# Audio.net
KiCad netlist of a schematic drawn in Altium Designer
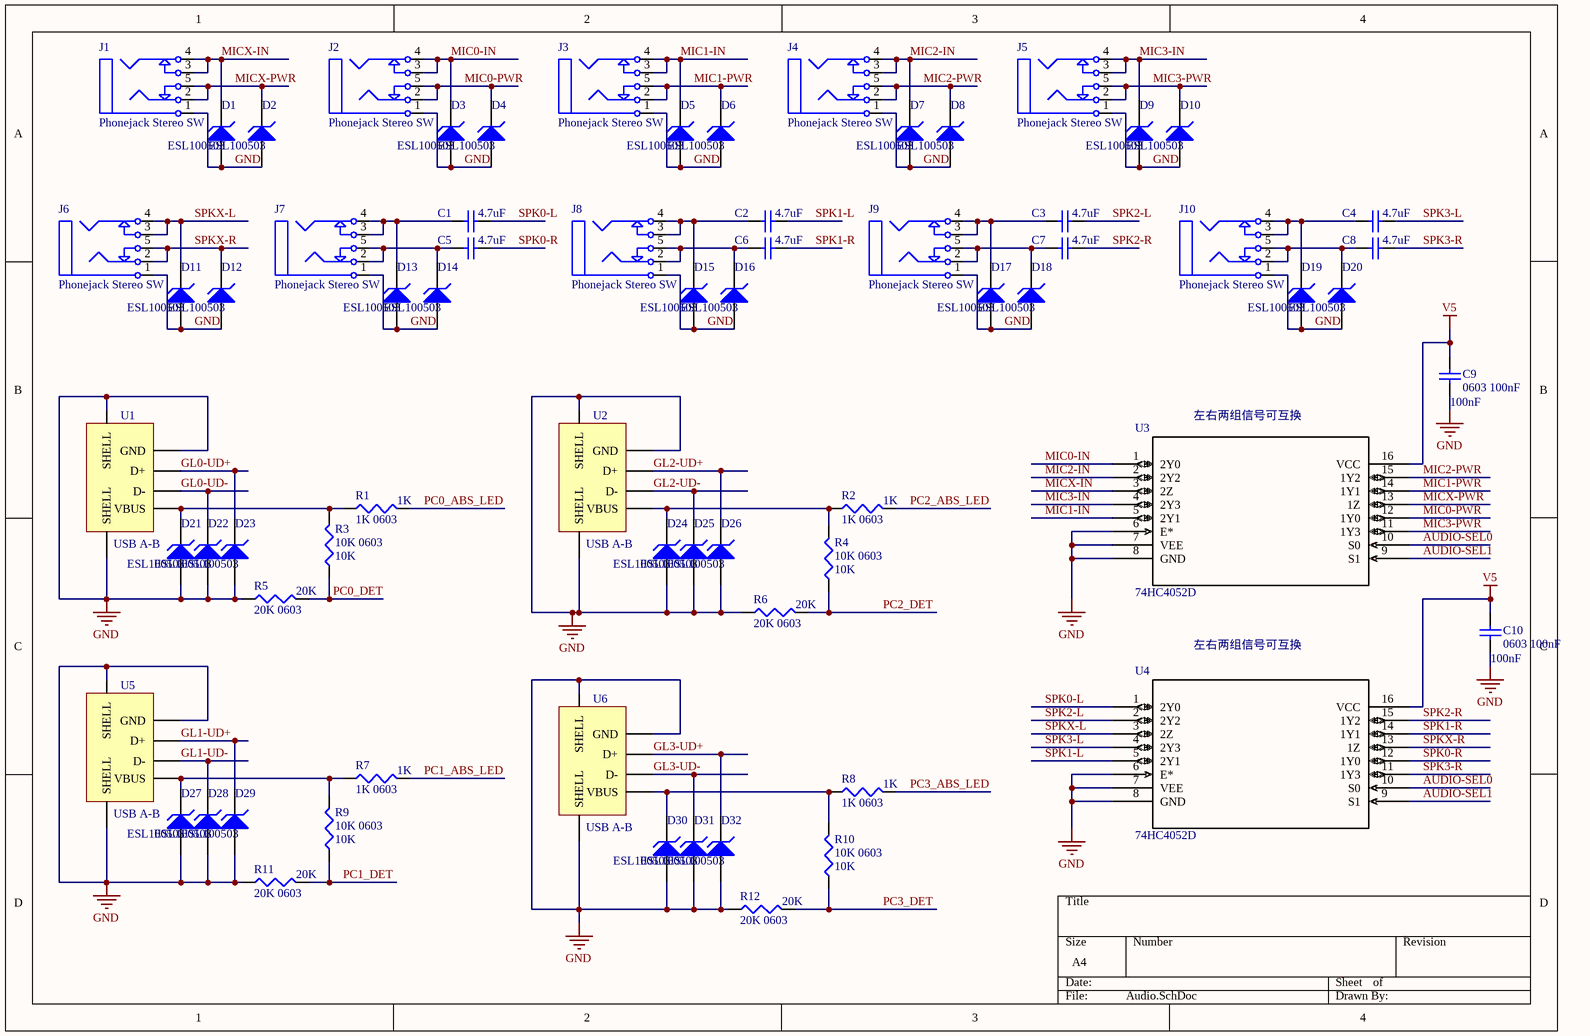
[diagram p0: Audio.SchDoc]

(export (version "E")
  (design (tool "Eeschema 10.0.6"))
  (components
    (comp (ref "C1")
      (value "4.7uF")
      (footprint "C0603")
      (description "Capacitor (Semiconductor SIM Model)")
      (fields (field (name "Comment") "0603 4.7uF") (field (name "PUBLISHER") "Altium Limited"))
      (libsource (lib "Miscellaneous Devices") (part "Cap Semi"))
    )
    (comp (ref "C2")
      (value "4.7uF")
      (footprint "C0603")
      (description "Capacitor (Semiconductor SIM Model)")
      (fields (field (name "Comment") "0603 4.7uF") (field (name "PUBLISHER") "Altium Limited"))
      (libsource (lib "Miscellaneous Devices") (part "Cap Semi"))
    )
    (comp (ref "C3")
      (value "4.7uF")
      (footprint "C0603")
      (description "Capacitor (Semiconductor SIM Model)")
      (fields (field (name "Comment") "0603 4.7uF") (field (name "PUBLISHER") "Altium Limited"))
      (libsource (lib "Miscellaneous Devices") (part "Cap Semi"))
    )
    (comp (ref "C4")
      (value "4.7uF")
      (footprint "C0603")
      (description "Capacitor (Semiconductor SIM Model)")
      (fields (field (name "Comment") "0603 4.7uF") (field (name "PUBLISHER") "Altium Limited"))
      (libsource (lib "Miscellaneous Devices") (part "Cap Semi"))
    )
    (comp (ref "C5")
      (value "4.7uF")
      (footprint "C0603")
      (description "Capacitor (Semiconductor SIM Model)")
      (fields (field (name "Comment") "0603 4.7uF") (field (name "PUBLISHER") "Altium Limited"))
      (libsource (lib "Miscellaneous Devices") (part "Cap Semi"))
    )
    (comp (ref "C6")
      (value "4.7uF")
      (footprint "C0603")
      (description "Capacitor (Semiconductor SIM Model)")
      (fields (field (name "Comment") "0603 4.7uF") (field (name "PUBLISHER") "Altium Limited"))
      (libsource (lib "Miscellaneous Devices") (part "Cap Semi"))
    )
    (comp (ref "C7")
      (value "4.7uF")
      (footprint "C0603")
      (description "Capacitor (Semiconductor SIM Model)")
      (fields (field (name "Comment") "0603 4.7uF") (field (name "PUBLISHER") "Altium Limited"))
      (libsource (lib "Miscellaneous Devices") (part "Cap Semi"))
    )
    (comp (ref "C8")
      (value "4.7uF")
      (footprint "C0603")
      (description "Capacitor (Semiconductor SIM Model)")
      (fields (field (name "Comment") "0603 4.7uF") (field (name "PUBLISHER") "Altium Limited"))
      (libsource (lib "Miscellaneous Devices") (part "Cap Semi"))
    )
    (comp (ref "C9")
      (value "0603 100nF")
      (footprint "C0603")
      (description "Capacitor (Semiconductor SIM Model)")
      (fields (field (name "ALTIUM_VALUE") "100nF") (field (name "PUBLISHER") "Altium Limited"))
      (libsource (lib "Miscellaneous Devices") (part "Cap Semi"))
    )
    (comp (ref "C10")
      (value "0603 100nF")
      (footprint "C0603")
      (description "Capacitor (Semiconductor SIM Model)")
      (fields (field (name "ALTIUM_VALUE") "100nF") (field (name "PUBLISHER") "Altium Limited"))
      (libsource (lib "Miscellaneous Devices") (part "Cap Semi"))
    )
    (comp (ref "D1")
      (value "ESL100503")
      (footprint "C0402")
      (fields (field (name "PUBLISHER") "Altium Limited"))
      (libsource (lib "Miscellaneous Devices") (part "D Zener"))
    )
    (comp (ref "D2")
      (value "ESL100503")
      (footprint "C0402")
      (fields (field (name "PUBLISHER") "Altium Limited"))
      (libsource (lib "Miscellaneous Devices") (part "D Zener"))
    )
    (comp (ref "D3")
      (value "ESL100503")
      (footprint "C0402")
      (fields (field (name "PUBLISHER") "Altium Limited"))
      (libsource (lib "Miscellaneous Devices") (part "D Zener"))
    )
    (comp (ref "D4")
      (value "ESL100503")
      (footprint "C0402")
      (fields (field (name "PUBLISHER") "Altium Limited"))
      (libsource (lib "Miscellaneous Devices") (part "D Zener"))
    )
    (comp (ref "D5")
      (value "ESL100503")
      (footprint "C0402")
      (fields (field (name "PUBLISHER") "Altium Limited"))
      (libsource (lib "Miscellaneous Devices") (part "D Zener"))
    )
    (comp (ref "D6")
      (value "ESL100503")
      (footprint "C0402")
      (fields (field (name "PUBLISHER") "Altium Limited"))
      (libsource (lib "Miscellaneous Devices") (part "D Zener"))
    )
    (comp (ref "D7")
      (value "ESL100503")
      (footprint "C0402")
      (fields (field (name "PUBLISHER") "Altium Limited"))
      (libsource (lib "Miscellaneous Devices") (part "D Zener"))
    )
    (comp (ref "D8")
      (value "ESL100503")
      (footprint "C0402")
      (fields (field (name "PUBLISHER") "Altium Limited"))
      (libsource (lib "Miscellaneous Devices") (part "D Zener"))
    )
    (comp (ref "D9")
      (value "ESL100503")
      (footprint "C0402")
      (fields (field (name "PUBLISHER") "Altium Limited"))
      (libsource (lib "Miscellaneous Devices") (part "D Zener"))
    )
    (comp (ref "D10")
      (value "ESL100503")
      (footprint "C0402")
      (fields (field (name "PUBLISHER") "Altium Limited"))
      (libsource (lib "Miscellaneous Devices") (part "D Zener"))
    )
    (comp (ref "D11")
      (value "ESL100503")
      (footprint "C0402")
      (fields (field (name "PUBLISHER") "Altium Limited"))
      (libsource (lib "Miscellaneous Devices") (part "D Zener"))
    )
    (comp (ref "D12")
      (value "ESL100503")
      (footprint "C0402")
      (fields (field (name "PUBLISHER") "Altium Limited"))
      (libsource (lib "Miscellaneous Devices") (part "D Zener"))
    )
    (comp (ref "D13")
      (value "ESL100503")
      (footprint "C0402")
      (fields (field (name "PUBLISHER") "Altium Limited"))
      (libsource (lib "Miscellaneous Devices") (part "D Zener"))
    )
    (comp (ref "D14")
      (value "ESL100503")
      (footprint "C0402")
      (fields (field (name "PUBLISHER") "Altium Limited"))
      (libsource (lib "Miscellaneous Devices") (part "D Zener"))
    )
    (comp (ref "D15")
      (value "ESL100503")
      (footprint "C0402")
      (fields (field (name "PUBLISHER") "Altium Limited"))
      (libsource (lib "Miscellaneous Devices") (part "D Zener"))
    )
    (comp (ref "D16")
      (value "ESL100503")
      (footprint "C0402")
      (fields (field (name "PUBLISHER") "Altium Limited"))
      (libsource (lib "Miscellaneous Devices") (part "D Zener"))
    )
    (comp (ref "D17")
      (value "ESL100503")
      (footprint "C0402")
      (fields (field (name "PUBLISHER") "Altium Limited"))
      (libsource (lib "Miscellaneous Devices") (part "D Zener"))
    )
    (comp (ref "D18")
      (value "ESL100503")
      (footprint "C0402")
      (fields (field (name "PUBLISHER") "Altium Limited"))
      (libsource (lib "Miscellaneous Devices") (part "D Zener"))
    )
    (comp (ref "D19")
      (value "ESL100503")
      (footprint "C0402")
      (fields (field (name "PUBLISHER") "Altium Limited"))
      (libsource (lib "Miscellaneous Devices") (part "D Zener"))
    )
    (comp (ref "D20")
      (value "ESL100503")
      (footprint "C0402")
      (fields (field (name "PUBLISHER") "Altium Limited"))
      (libsource (lib "Miscellaneous Devices") (part "D Zener"))
    )
    (comp (ref "D21")
      (value "ESL100503")
      (footprint "C0402")
      (fields (field (name "PUBLISHER") "Altium Limited"))
      (libsource (lib "Miscellaneous Devices") (part "D Zener"))
    )
    (comp (ref "D22")
      (value "ESL100503")
      (footprint "C0402")
      (fields (field (name "PUBLISHER") "Altium Limited"))
      (libsource (lib "Miscellaneous Devices") (part "D Zener"))
    )
    (comp (ref "D23")
      (value "ESL100503")
      (footprint "C0402")
      (fields (field (name "PUBLISHER") "Altium Limited"))
      (libsource (lib "Miscellaneous Devices") (part "D Zener"))
    )
    (comp (ref "D24")
      (value "ESL100503")
      (footprint "C0402")
      (fields (field (name "PUBLISHER") "Altium Limited"))
      (libsource (lib "Miscellaneous Devices") (part "D Zener"))
    )
    (comp (ref "D25")
      (value "ESL100503")
      (footprint "C0402")
      (fields (field (name "PUBLISHER") "Altium Limited"))
      (libsource (lib "Miscellaneous Devices") (part "D Zener"))
    )
    (comp (ref "D26")
      (value "ESL100503")
      (footprint "C0402")
      (fields (field (name "PUBLISHER") "Altium Limited"))
      (libsource (lib "Miscellaneous Devices") (part "D Zener"))
    )
    (comp (ref "D27")
      (value "ESL100503")
      (footprint "C0402")
      (fields (field (name "PUBLISHER") "Altium Limited"))
      (libsource (lib "Miscellaneous Devices") (part "D Zener"))
    )
    (comp (ref "D28")
      (value "ESL100503")
      (footprint "C0402")
      (fields (field (name "PUBLISHER") "Altium Limited"))
      (libsource (lib "Miscellaneous Devices") (part "D Zener"))
    )
    (comp (ref "D29")
      (value "ESL100503")
      (footprint "C0402")
      (fields (field (name "PUBLISHER") "Altium Limited"))
      (libsource (lib "Miscellaneous Devices") (part "D Zener"))
    )
    (comp (ref "D30")
      (value "ESL100503")
      (footprint "C0402")
      (fields (field (name "PUBLISHER") "Altium Limited"))
      (libsource (lib "Miscellaneous Devices") (part "D Zener"))
    )
    (comp (ref "D31")
      (value "ESL100503")
      (footprint "C0402")
      (fields (field (name "PUBLISHER") "Altium Limited"))
      (libsource (lib "Miscellaneous Devices") (part "D Zener"))
    )
    (comp (ref "D32")
      (value "ESL100503")
      (footprint "C0402")
      (fields (field (name "PUBLISHER") "Altium Limited"))
      (libsource (lib "Miscellaneous Devices") (part "D Zener"))
    )
    (comp (ref "J1")
      (value "Phonejack Stereo SW")
      (footprint "ST-3150-5N")
      (description "3-Conductor Jack with 2 break contacts (normals) and 2 auxiliary make contacts")
      (fields (field (name "PUBLISHER") "Altium Limited"))
      (libsource (lib "Miscellaneous Connectors") (part "Phonejack Stereo SW"))
    )
    (comp (ref "J2")
      (value "Phonejack Stereo SW")
      (footprint "ST-3150-5N")
      (description "3-Conductor Jack with 2 break contacts (normals) and 2 auxiliary make contacts")
      (fields (field (name "PUBLISHER") "Altium Limited"))
      (libsource (lib "Miscellaneous Connectors") (part "Phonejack Stereo SW"))
    )
    (comp (ref "J3")
      (value "Phonejack Stereo SW")
      (footprint "ST-3150-5N")
      (description "3-Conductor Jack with 2 break contacts (normals) and 2 auxiliary make contacts")
      (fields (field (name "PUBLISHER") "Altium Limited"))
      (libsource (lib "Miscellaneous Connectors") (part "Phonejack Stereo SW"))
    )
    (comp (ref "J4")
      (value "Phonejack Stereo SW")
      (footprint "ST-3150-5N")
      (description "3-Conductor Jack with 2 break contacts (normals) and 2 auxiliary make contacts")
      (fields (field (name "PUBLISHER") "Altium Limited"))
      (libsource (lib "Miscellaneous Connectors") (part "Phonejack Stereo SW"))
    )
    (comp (ref "J5")
      (value "Phonejack Stereo SW")
      (footprint "ST-3150-5N")
      (description "3-Conductor Jack with 2 break contacts (normals) and 2 auxiliary make contacts")
      (fields (field (name "PUBLISHER") "Altium Limited"))
      (libsource (lib "Miscellaneous Connectors") (part "Phonejack Stereo SW"))
    )
    (comp (ref "J6")
      (value "Phonejack Stereo SW")
      (footprint "ST-3150-5N")
      (description "3-Conductor Jack with 2 break contacts (normals) and 2 auxiliary make contacts")
      (fields (field (name "PUBLISHER") "Altium Limited"))
      (libsource (lib "Miscellaneous Connectors") (part "Phonejack Stereo SW"))
    )
    (comp (ref "J7")
      (value "Phonejack Stereo SW")
      (footprint "ST-3150-5N")
      (description "3-Conductor Jack with 2 break contacts (normals) and 2 auxiliary make contacts")
      (fields (field (name "PUBLISHER") "Altium Limited"))
      (libsource (lib "Miscellaneous Connectors") (part "Phonejack Stereo SW"))
    )
    (comp (ref "J8")
      (value "Phonejack Stereo SW")
      (footprint "ST-3150-5N")
      (description "3-Conductor Jack with 2 break contacts (normals) and 2 auxiliary make contacts")
      (fields (field (name "PUBLISHER") "Altium Limited"))
      (libsource (lib "Miscellaneous Connectors") (part "Phonejack Stereo SW"))
    )
    (comp (ref "J9")
      (value "Phonejack Stereo SW")
      (footprint "ST-3150-5N")
      (description "3-Conductor Jack with 2 break contacts (normals) and 2 auxiliary make contacts")
      (fields (field (name "PUBLISHER") "Altium Limited"))
      (libsource (lib "Miscellaneous Connectors") (part "Phonejack Stereo SW"))
    )
    (comp (ref "J10")
      (value "Phonejack Stereo SW")
      (footprint "ST-3150-5N")
      (description "3-Conductor Jack with 2 break contacts (normals) and 2 auxiliary make contacts")
      (fields (field (name "PUBLISHER") "Altium Limited"))
      (libsource (lib "Miscellaneous Connectors") (part "Phonejack Stereo SW"))
    )
    (comp (ref "R1")
      (value "1K 0603")
      (footprint "R0603")
      (description "Resistor")
      (fields (field (name "ALTIUM_VALUE") "1K") (field (name "PUBLISHER") "Altium Limited"))
      (libsource (lib "Miscellaneous Devices") (part "Res3"))
    )
    (comp (ref "R2")
      (value "1K 0603")
      (footprint "R0603")
      (description "Resistor")
      (fields (field (name "ALTIUM_VALUE") "1K") (field (name "PUBLISHER") "Altium Limited"))
      (libsource (lib "Miscellaneous Devices") (part "Res3"))
    )
    (comp (ref "R3")
      (value "10K 0603")
      (footprint "R0603")
      (description "Resistor")
      (fields (field (name "ALTIUM_VALUE") "10K") (field (name "PUBLISHER") "Altium Limited"))
      (libsource (lib "Miscellaneous Devices") (part "Res3"))
    )
    (comp (ref "R4")
      (value "10K 0603")
      (footprint "R0603")
      (description "Resistor")
      (fields (field (name "ALTIUM_VALUE") "10K") (field (name "PUBLISHER") "Altium Limited"))
      (libsource (lib "Miscellaneous Devices") (part "Res3"))
    )
    (comp (ref "R5")
      (value "20K 0603")
      (footprint "R0603")
      (description "Resistor")
      (fields (field (name "ALTIUM_VALUE") "20K") (field (name "PUBLISHER") "Altium Limited"))
      (libsource (lib "Miscellaneous Devices") (part "Res3"))
    )
    (comp (ref "R6")
      (value "20K 0603")
      (footprint "R0603")
      (description "Resistor")
      (fields (field (name "ALTIUM_VALUE") "20K") (field (name "PUBLISHER") "Altium Limited"))
      (libsource (lib "Miscellaneous Devices") (part "Res3"))
    )
    (comp (ref "R7")
      (value "1K 0603")
      (footprint "R0603")
      (description "Resistor")
      (fields (field (name "ALTIUM_VALUE") "1K") (field (name "PUBLISHER") "Altium Limited"))
      (libsource (lib "Miscellaneous Devices") (part "Res3"))
    )
    (comp (ref "R8")
      (value "1K 0603")
      (footprint "R0603")
      (description "Resistor")
      (fields (field (name "ALTIUM_VALUE") "1K") (field (name "PUBLISHER") "Altium Limited"))
      (libsource (lib "Miscellaneous Devices") (part "Res3"))
    )
    (comp (ref "R9")
      (value "10K 0603")
      (footprint "R0603")
      (description "Resistor")
      (fields (field (name "ALTIUM_VALUE") "10K") (field (name "PUBLISHER") "Altium Limited"))
      (libsource (lib "Miscellaneous Devices") (part "Res3"))
    )
    (comp (ref "R10")
      (value "10K 0603")
      (footprint "R0603")
      (description "Resistor")
      (fields (field (name "ALTIUM_VALUE") "10K") (field (name "PUBLISHER") "Altium Limited"))
      (libsource (lib "Miscellaneous Devices") (part "Res3"))
    )
    (comp (ref "R11")
      (value "20K 0603")
      (footprint "R0603")
      (description "Resistor")
      (fields (field (name "ALTIUM_VALUE") "20K") (field (name "PUBLISHER") "Altium Limited"))
      (libsource (lib "Miscellaneous Devices") (part "Res3"))
    )
    (comp (ref "R12")
      (value "20K 0603")
      (footprint "R0603")
      (description "Resistor")
      (fields (field (name "ALTIUM_VALUE") "20K") (field (name "PUBLISHER") "Altium Limited"))
      (libsource (lib "Miscellaneous Devices") (part "Res3"))
    )
    (comp (ref "U1") (value "USB A-B") (footprint "USB-A") (libsource (lib "Common Device") (part "USB A-B")))
    (comp (ref "U2") (value "USB A-B") (footprint "USB-A") (libsource (lib "Common Device") (part "USB A-B")))
    (comp (ref "U3")
      (value "74HC4052D")
      (footprint "SOT109-1")
      (description "Imported")
      (fields (field (name "MANUFACTURER_PART_NUMBER") "74hc4052d"))
      (libsource (lib "74HC4052D") (part "74HC4052D"))
    )
    (comp (ref "U4")
      (value "74HC4052D")
      (footprint "SOT109-1")
      (description "Imported")
      (fields (field (name "MANUFACTURER_PART_NUMBER") "74hc4052d"))
      (libsource (lib "74HC4052D") (part "74HC4052D"))
    )
    (comp (ref "U5") (value "USB A-B") (footprint "USB-A") (libsource (lib "Common Device") (part "USB A-B")))
    (comp (ref "U6") (value "USB A-B") (footprint "USB-A") (libsource (lib "Common Device") (part "USB A-B")))
  )
  (nets
    (net (code "1") (name "/AUDIO-SEL0") (class "Default")
      (node (ref "U3") (pin "10") (pinfunction "S0_10") (pintype "input"))
      (node (ref "U4") (pin "10") (pinfunction "S0_10") (pintype "input"))
    )
    (net (code "2") (name "/AUDIO-SEL1") (class "Default")
      (node (ref "U3") (pin "9") (pinfunction "S1_9") (pintype "input"))
      (node (ref "U4") (pin "9") (pinfunction "S1_9") (pintype "input"))
    )
    (net (code "3") (name "/GL0-UD+") (class "Default")
      (node (ref "D23") (pin "2") (pinfunction "K_2") (pintype "passive"))
      (node (ref "U1") (pin "3") (pinfunction "D+_3") (pintype "passive"))
    )
    (net (code "4") (name "/GL0-UD-") (class "Default")
      (node (ref "D22") (pin "2") (pinfunction "K_2") (pintype "passive"))
      (node (ref "U1") (pin "2") (pinfunction "D-_2") (pintype "passive"))
    )
    (net (code "5") (name "/GL1-UD+") (class "Default")
      (node (ref "D29") (pin "2") (pinfunction "K_2") (pintype "passive"))
      (node (ref "U5") (pin "3") (pinfunction "D+_3") (pintype "passive"))
    )
    (net (code "6") (name "/GL1-UD-") (class "Default")
      (node (ref "D28") (pin "2") (pinfunction "K_2") (pintype "passive"))
      (node (ref "U5") (pin "2") (pinfunction "D-_2") (pintype "passive"))
    )
    (net (code "7") (name "/GL2-UD+") (class "Default")
      (node (ref "D26") (pin "2") (pinfunction "K_2") (pintype "passive"))
      (node (ref "U2") (pin "3") (pinfunction "D+_3") (pintype "passive"))
    )
    (net (code "8") (name "/GL2-UD-") (class "Default")
      (node (ref "D25") (pin "2") (pinfunction "K_2") (pintype "passive"))
      (node (ref "U2") (pin "2") (pinfunction "D-_2") (pintype "passive"))
    )
    (net (code "9") (name "/GL3-UD+") (class "Default")
      (node (ref "D32") (pin "2") (pinfunction "K_2") (pintype "passive"))
      (node (ref "U6") (pin "3") (pinfunction "D+_3") (pintype "passive"))
    )
    (net (code "10") (name "/GL3-UD-") (class "Default")
      (node (ref "D31") (pin "2") (pinfunction "K_2") (pintype "passive"))
      (node (ref "U6") (pin "2") (pinfunction "D-_2") (pintype "passive"))
    )
    (net (code "11") (name "/MIC0-IN") (class "Default")
      (node (ref "D3") (pin "2") (pinfunction "K_2") (pintype "passive"))
      (node (ref "J2") (pin "3") (pinfunction "3_3") (pintype "passive"))
      (node (ref "J2") (pin "4") (pinfunction "4_4") (pintype "passive"))
      (node (ref "U3") (pin "1") (pinfunction "2Y0_1") (pintype "bidirectional"))
    )
    (net (code "12") (name "/MIC0-PWR") (class "Default")
      (node (ref "D4") (pin "2") (pinfunction "K_2") (pintype "passive"))
      (node (ref "J2") (pin "2") (pinfunction "2_2") (pintype "passive"))
      (node (ref "J2") (pin "5") (pinfunction "5_5") (pintype "passive"))
      (node (ref "U3") (pin "12") (pinfunction "1Y0_12") (pintype "bidirectional"))
    )
    (net (code "13") (name "/MIC1-IN") (class "Default")
      (node (ref "D5") (pin "2") (pinfunction "K_2") (pintype "passive"))
      (node (ref "J3") (pin "3") (pinfunction "3_3") (pintype "passive"))
      (node (ref "J3") (pin "4") (pinfunction "4_4") (pintype "passive"))
      (node (ref "U3") (pin "5") (pinfunction "2Y1_5") (pintype "bidirectional"))
    )
    (net (code "14") (name "/MIC1-PWR") (class "Default")
      (node (ref "D6") (pin "2") (pinfunction "K_2") (pintype "passive"))
      (node (ref "J3") (pin "2") (pinfunction "2_2") (pintype "passive"))
      (node (ref "J3") (pin "5") (pinfunction "5_5") (pintype "passive"))
      (node (ref "U3") (pin "14") (pinfunction "1Y1_14") (pintype "bidirectional"))
    )
    (net (code "15") (name "/MIC2-IN") (class "Default")
      (node (ref "D7") (pin "2") (pinfunction "K_2") (pintype "passive"))
      (node (ref "J4") (pin "3") (pinfunction "3_3") (pintype "passive"))
      (node (ref "J4") (pin "4") (pinfunction "4_4") (pintype "passive"))
      (node (ref "U3") (pin "2") (pinfunction "2Y2_2") (pintype "bidirectional"))
    )
    (net (code "16") (name "/MIC2-PWR") (class "Default")
      (node (ref "D8") (pin "2") (pinfunction "K_2") (pintype "passive"))
      (node (ref "J4") (pin "2") (pinfunction "2_2") (pintype "passive"))
      (node (ref "J4") (pin "5") (pinfunction "5_5") (pintype "passive"))
      (node (ref "U3") (pin "15") (pinfunction "1Y2_15") (pintype "bidirectional"))
    )
    (net (code "17") (name "/MIC3-IN") (class "Default")
      (node (ref "D9") (pin "2") (pinfunction "K_2") (pintype "passive"))
      (node (ref "J5") (pin "3") (pinfunction "3_3") (pintype "passive"))
      (node (ref "J5") (pin "4") (pinfunction "4_4") (pintype "passive"))
      (node (ref "U3") (pin "4") (pinfunction "2Y3_4") (pintype "bidirectional"))
    )
    (net (code "18") (name "/MIC3-PWR") (class "Default")
      (node (ref "D10") (pin "2") (pinfunction "K_2") (pintype "passive"))
      (node (ref "J5") (pin "2") (pinfunction "2_2") (pintype "passive"))
      (node (ref "J5") (pin "5") (pinfunction "5_5") (pintype "passive"))
      (node (ref "U3") (pin "11") (pinfunction "1Y3_11") (pintype "bidirectional"))
    )
    (net (code "19") (name "/MICX-IN") (class "Default")
      (node (ref "D1") (pin "2") (pinfunction "K_2") (pintype "passive"))
      (node (ref "J1") (pin "3") (pinfunction "3_3") (pintype "passive"))
      (node (ref "J1") (pin "4") (pinfunction "4_4") (pintype "passive"))
      (node (ref "U3") (pin "3") (pinfunction "2Z_3") (pintype "bidirectional"))
    )
    (net (code "20") (name "/MICX-PWR") (class "Default")
      (node (ref "D2") (pin "2") (pinfunction "K_2") (pintype "passive"))
      (node (ref "J1") (pin "2") (pinfunction "2_2") (pintype "passive"))
      (node (ref "J1") (pin "5") (pinfunction "5_5") (pintype "passive"))
      (node (ref "U3") (pin "13") (pinfunction "1Z_13") (pintype "bidirectional"))
    )
    (net (code "21") (name "/PC0_ABS_LED") (class "Default")
      (node (ref "R1") (pin "2") (pinfunction "2_2") (pintype "passive"))
    )
    (net (code "22") (name "/PC0_DET") (class "Default")
      (node (ref "R3") (pin "1") (pinfunction "1_1") (pintype "passive"))
      (node (ref "R5") (pin "2") (pinfunction "2_2") (pintype "passive"))
    )
    (net (code "23") (name "/PC1_ABS_LED") (class "Default")
      (node (ref "R7") (pin "2") (pinfunction "2_2") (pintype "passive"))
    )
    (net (code "24") (name "/PC1_DET") (class "Default")
      (node (ref "R11") (pin "2") (pinfunction "2_2") (pintype "passive"))
      (node (ref "R9") (pin "1") (pinfunction "1_1") (pintype "passive"))
    )
    (net (code "25") (name "/PC2_ABS_LED") (class "Default")
      (node (ref "R2") (pin "2") (pinfunction "2_2") (pintype "passive"))
    )
    (net (code "26") (name "/PC2_DET") (class "Default")
      (node (ref "R4") (pin "1") (pinfunction "1_1") (pintype "passive"))
      (node (ref "R6") (pin "2") (pinfunction "2_2") (pintype "passive"))
    )
    (net (code "27") (name "/PC3_ABS_LED") (class "Default")
      (node (ref "R8") (pin "2") (pinfunction "2_2") (pintype "passive"))
    )
    (net (code "28") (name "/PC3_DET") (class "Default")
      (node (ref "R10") (pin "1") (pinfunction "1_1") (pintype "passive"))
      (node (ref "R12") (pin "2") (pinfunction "2_2") (pintype "passive"))
    )
    (net (code "29") (name "/SPK0-L") (class "Default")
      (node (ref "C1") (pin "1") (pinfunction "1_1") (pintype "passive"))
      (node (ref "U4") (pin "1") (pinfunction "2Y0_1") (pintype "bidirectional"))
    )
    (net (code "30") (name "/SPK0-R") (class "Default")
      (node (ref "C5") (pin "1") (pinfunction "1_1") (pintype "passive"))
      (node (ref "U4") (pin "12") (pinfunction "1Y0_12") (pintype "bidirectional"))
    )
    (net (code "31") (name "/SPK1-L") (class "Default")
      (node (ref "C2") (pin "1") (pinfunction "1_1") (pintype "passive"))
      (node (ref "U4") (pin "5") (pinfunction "2Y1_5") (pintype "bidirectional"))
    )
    (net (code "32") (name "/SPK1-R") (class "Default")
      (node (ref "C6") (pin "1") (pinfunction "1_1") (pintype "passive"))
      (node (ref "U4") (pin "14") (pinfunction "1Y1_14") (pintype "bidirectional"))
    )
    (net (code "33") (name "/SPK2-L") (class "Default")
      (node (ref "C3") (pin "1") (pinfunction "1_1") (pintype "passive"))
      (node (ref "U4") (pin "2") (pinfunction "2Y2_2") (pintype "bidirectional"))
    )
    (net (code "34") (name "/SPK2-R") (class "Default")
      (node (ref "C7") (pin "1") (pinfunction "1_1") (pintype "passive"))
      (node (ref "U4") (pin "15") (pinfunction "1Y2_15") (pintype "bidirectional"))
    )
    (net (code "35") (name "/SPK3-L") (class "Default")
      (node (ref "C4") (pin "1") (pinfunction "1_1") (pintype "passive"))
      (node (ref "U4") (pin "4") (pinfunction "2Y3_4") (pintype "bidirectional"))
    )
    (net (code "36") (name "/SPK3-R") (class "Default")
      (node (ref "C8") (pin "1") (pinfunction "1_1") (pintype "passive"))
      (node (ref "U4") (pin "11") (pinfunction "1Y3_11") (pintype "bidirectional"))
    )
    (net (code "37") (name "/SPKX-L") (class "Default")
      (node (ref "D11") (pin "2") (pinfunction "K_2") (pintype "passive"))
      (node (ref "J6") (pin "3") (pinfunction "3_3") (pintype "passive"))
      (node (ref "J6") (pin "4") (pinfunction "4_4") (pintype "passive"))
      (node (ref "U4") (pin "3") (pinfunction "2Z_3") (pintype "bidirectional"))
    )
    (net (code "38") (name "/SPKX-R") (class "Default")
      (node (ref "D12") (pin "2") (pinfunction "K_2") (pintype "passive"))
      (node (ref "J6") (pin "2") (pinfunction "2_2") (pintype "passive"))
      (node (ref "J6") (pin "5") (pinfunction "5_5") (pintype "passive"))
      (node (ref "U4") (pin "13") (pinfunction "1Z_13") (pintype "bidirectional"))
    )
    (net (code "39") (name "GND") (class "Default")
      (node (ref "C10") (pin "1") (pinfunction "1_1") (pintype "passive"))
      (node (ref "C9") (pin "1") (pinfunction "1_1") (pintype "passive"))
      (node (ref "D1") (pin "1") (pinfunction "A_1") (pintype "passive"))
      (node (ref "D10") (pin "1") (pinfunction "A_1") (pintype "passive"))
      (node (ref "D11") (pin "1") (pinfunction "A_1") (pintype "passive"))
      (node (ref "D12") (pin "1") (pinfunction "A_1") (pintype "passive"))
      (node (ref "D13") (pin "1") (pinfunction "A_1") (pintype "passive"))
      (node (ref "D14") (pin "1") (pinfunction "A_1") (pintype "passive"))
      (node (ref "D15") (pin "1") (pinfunction "A_1") (pintype "passive"))
      (node (ref "D16") (pin "1") (pinfunction "A_1") (pintype "passive"))
      (node (ref "D17") (pin "1") (pinfunction "A_1") (pintype "passive"))
      (node (ref "D18") (pin "1") (pinfunction "A_1") (pintype "passive"))
      (node (ref "D19") (pin "1") (pinfunction "A_1") (pintype "passive"))
      (node (ref "D2") (pin "1") (pinfunction "A_1") (pintype "passive"))
      (node (ref "D20") (pin "1") (pinfunction "A_1") (pintype "passive"))
      (node (ref "D21") (pin "1") (pinfunction "A_1") (pintype "passive"))
      (node (ref "D22") (pin "1") (pinfunction "A_1") (pintype "passive"))
      (node (ref "D23") (pin "1") (pinfunction "A_1") (pintype "passive"))
      (node (ref "D24") (pin "1") (pinfunction "A_1") (pintype "passive"))
      (node (ref "D25") (pin "1") (pinfunction "A_1") (pintype "passive"))
      (node (ref "D26") (pin "1") (pinfunction "A_1") (pintype "passive"))
      (node (ref "D27") (pin "1") (pinfunction "A_1") (pintype "passive"))
      (node (ref "D28") (pin "1") (pinfunction "A_1") (pintype "passive"))
      (node (ref "D29") (pin "1") (pinfunction "A_1") (pintype "passive"))
      (node (ref "D3") (pin "1") (pinfunction "A_1") (pintype "passive"))
      (node (ref "D30") (pin "1") (pinfunction "A_1") (pintype "passive"))
      (node (ref "D31") (pin "1") (pinfunction "A_1") (pintype "passive"))
      (node (ref "D32") (pin "1") (pinfunction "A_1") (pintype "passive"))
      (node (ref "D4") (pin "1") (pinfunction "A_1") (pintype "passive"))
      (node (ref "D5") (pin "1") (pinfunction "A_1") (pintype "passive"))
      (node (ref "D6") (pin "1") (pinfunction "A_1") (pintype "passive"))
      (node (ref "D7") (pin "1") (pinfunction "A_1") (pintype "passive"))
      (node (ref "D8") (pin "1") (pinfunction "A_1") (pintype "passive"))
      (node (ref "D9") (pin "1") (pinfunction "A_1") (pintype "passive"))
      (node (ref "J1") (pin "1") (pinfunction "1_1") (pintype "passive"))
      (node (ref "J10") (pin "1") (pinfunction "1_1") (pintype "passive"))
      (node (ref "J2") (pin "1") (pinfunction "1_1") (pintype "passive"))
      (node (ref "J3") (pin "1") (pinfunction "1_1") (pintype "passive"))
      (node (ref "J4") (pin "1") (pinfunction "1_1") (pintype "passive"))
      (node (ref "J5") (pin "1") (pinfunction "1_1") (pintype "passive"))
      (node (ref "J6") (pin "1") (pinfunction "1_1") (pintype "passive"))
      (node (ref "J7") (pin "1") (pinfunction "1_1") (pintype "passive"))
      (node (ref "J8") (pin "1") (pinfunction "1_1") (pintype "passive"))
      (node (ref "J9") (pin "1") (pinfunction "1_1") (pintype "passive"))
      (node (ref "R11") (pin "1") (pinfunction "1_1") (pintype "passive"))
      (node (ref "R12") (pin "1") (pinfunction "1_1") (pintype "passive"))
      (node (ref "R5") (pin "1") (pinfunction "1_1") (pintype "passive"))
      (node (ref "R6") (pin "1") (pinfunction "1_1") (pintype "passive"))
      (node (ref "U1") (pin "4") (pinfunction "GND_4") (pintype "passive"))
      (node (ref "U1") (pin "5") (pinfunction "SHELL_5") (pintype "passive"))
      (node (ref "U1") (pin "6") (pinfunction "SHELL_6") (pintype "passive"))
      (node (ref "U2") (pin "4") (pinfunction "GND_4") (pintype "passive"))
      (node (ref "U2") (pin "5") (pinfunction "SHELL_5") (pintype "passive"))
      (node (ref "U2") (pin "6") (pinfunction "SHELL_6") (pintype "passive"))
      (node (ref "U3") (pin "6") (pinfunction "E*_6") (pintype "input"))
      (node (ref "U3") (pin "7") (pinfunction "VEE_7") (pintype "power_in"))
      (node (ref "U3") (pin "8") (pinfunction "GND_8") (pintype "power_in"))
      (node (ref "U4") (pin "6") (pinfunction "E*_6") (pintype "input"))
      (node (ref "U4") (pin "7") (pinfunction "VEE_7") (pintype "power_in"))
      (node (ref "U4") (pin "8") (pinfunction "GND_8") (pintype "power_in"))
      (node (ref "U5") (pin "4") (pinfunction "GND_4") (pintype "passive"))
      (node (ref "U5") (pin "5") (pinfunction "SHELL_5") (pintype "passive"))
      (node (ref "U5") (pin "6") (pinfunction "SHELL_6") (pintype "passive"))
      (node (ref "U6") (pin "4") (pinfunction "GND_4") (pintype "passive"))
      (node (ref "U6") (pin "5") (pinfunction "SHELL_5") (pintype "passive"))
      (node (ref "U6") (pin "6") (pinfunction "SHELL_6") (pintype "passive"))
    )
    (net (code "40") (name "Net-(D13-K)") (class "Default")
      (node (ref "C1") (pin "2") (pinfunction "2_2") (pintype "passive"))
      (node (ref "D13") (pin "2") (pinfunction "K_2") (pintype "passive"))
      (node (ref "J7") (pin "3") (pinfunction "3_3") (pintype "passive"))
      (node (ref "J7") (pin "4") (pinfunction "4_4") (pintype "passive"))
    )
    (net (code "41") (name "Net-(D14-K)") (class "Default")
      (node (ref "C5") (pin "2") (pinfunction "2_2") (pintype "passive"))
      (node (ref "D14") (pin "2") (pinfunction "K_2") (pintype "passive"))
      (node (ref "J7") (pin "2") (pinfunction "2_2") (pintype "passive"))
      (node (ref "J7") (pin "5") (pinfunction "5_5") (pintype "passive"))
    )
    (net (code "42") (name "Net-(D15-K)") (class "Default")
      (node (ref "C2") (pin "2") (pinfunction "2_2") (pintype "passive"))
      (node (ref "D15") (pin "2") (pinfunction "K_2") (pintype "passive"))
      (node (ref "J8") (pin "3") (pinfunction "3_3") (pintype "passive"))
      (node (ref "J8") (pin "4") (pinfunction "4_4") (pintype "passive"))
    )
    (net (code "43") (name "Net-(D16-K)") (class "Default")
      (node (ref "C6") (pin "2") (pinfunction "2_2") (pintype "passive"))
      (node (ref "D16") (pin "2") (pinfunction "K_2") (pintype "passive"))
      (node (ref "J8") (pin "2") (pinfunction "2_2") (pintype "passive"))
      (node (ref "J8") (pin "5") (pinfunction "5_5") (pintype "passive"))
    )
    (net (code "44") (name "Net-(D17-K)") (class "Default")
      (node (ref "C3") (pin "2") (pinfunction "2_2") (pintype "passive"))
      (node (ref "D17") (pin "2") (pinfunction "K_2") (pintype "passive"))
      (node (ref "J9") (pin "3") (pinfunction "3_3") (pintype "passive"))
      (node (ref "J9") (pin "4") (pinfunction "4_4") (pintype "passive"))
    )
    (net (code "45") (name "Net-(D18-K)") (class "Default")
      (node (ref "C7") (pin "2") (pinfunction "2_2") (pintype "passive"))
      (node (ref "D18") (pin "2") (pinfunction "K_2") (pintype "passive"))
      (node (ref "J9") (pin "2") (pinfunction "2_2") (pintype "passive"))
      (node (ref "J9") (pin "5") (pinfunction "5_5") (pintype "passive"))
    )
    (net (code "46") (name "Net-(D19-K)") (class "Default")
      (node (ref "C4") (pin "2") (pinfunction "2_2") (pintype "passive"))
      (node (ref "D19") (pin "2") (pinfunction "K_2") (pintype "passive"))
      (node (ref "J10") (pin "3") (pinfunction "3_3") (pintype "passive"))
      (node (ref "J10") (pin "4") (pinfunction "4_4") (pintype "passive"))
    )
    (net (code "47") (name "Net-(D20-K)") (class "Default")
      (node (ref "C8") (pin "2") (pinfunction "2_2") (pintype "passive"))
      (node (ref "D20") (pin "2") (pinfunction "K_2") (pintype "passive"))
      (node (ref "J10") (pin "2") (pinfunction "2_2") (pintype "passive"))
      (node (ref "J10") (pin "5") (pinfunction "5_5") (pintype "passive"))
    )
    (net (code "48") (name "Net-(D21-K)") (class "Default")
      (node (ref "D21") (pin "2") (pinfunction "K_2") (pintype "passive"))
      (node (ref "R1") (pin "1") (pinfunction "1_1") (pintype "passive"))
      (node (ref "R3") (pin "2") (pinfunction "2_2") (pintype "passive"))
      (node (ref "U1") (pin "1") (pinfunction "VBUS_1") (pintype "passive"))
    )
    (net (code "49") (name "Net-(D24-K)") (class "Default")
      (node (ref "D24") (pin "2") (pinfunction "K_2") (pintype "passive"))
      (node (ref "R2") (pin "1") (pinfunction "1_1") (pintype "passive"))
      (node (ref "R4") (pin "2") (pinfunction "2_2") (pintype "passive"))
      (node (ref "U2") (pin "1") (pinfunction "VBUS_1") (pintype "passive"))
    )
    (net (code "50") (name "Net-(D27-K)") (class "Default")
      (node (ref "D27") (pin "2") (pinfunction "K_2") (pintype "passive"))
      (node (ref "R7") (pin "1") (pinfunction "1_1") (pintype "passive"))
      (node (ref "R9") (pin "2") (pinfunction "2_2") (pintype "passive"))
      (node (ref "U5") (pin "1") (pinfunction "VBUS_1") (pintype "passive"))
    )
    (net (code "51") (name "Net-(D30-K)") (class "Default")
      (node (ref "D30") (pin "2") (pinfunction "K_2") (pintype "passive"))
      (node (ref "R10") (pin "2") (pinfunction "2_2") (pintype "passive"))
      (node (ref "R8") (pin "1") (pinfunction "1_1") (pintype "passive"))
      (node (ref "U6") (pin "1") (pinfunction "VBUS_1") (pintype "passive"))
    )
    (net (code "52") (name "V5") (class "Default")
      (node (ref "C10") (pin "2") (pinfunction "2_2") (pintype "passive"))
      (node (ref "C9") (pin "2") (pinfunction "2_2") (pintype "passive"))
      (node (ref "U3") (pin "16") (pinfunction "VCC_16") (pintype "power_in"))
      (node (ref "U4") (pin "16") (pinfunction "VCC_16") (pintype "power_in"))
    )
  )
)
